# ddrive-esp-deadrail-1-1.net
KiCad netlist of a schematic drawn in EAGLE
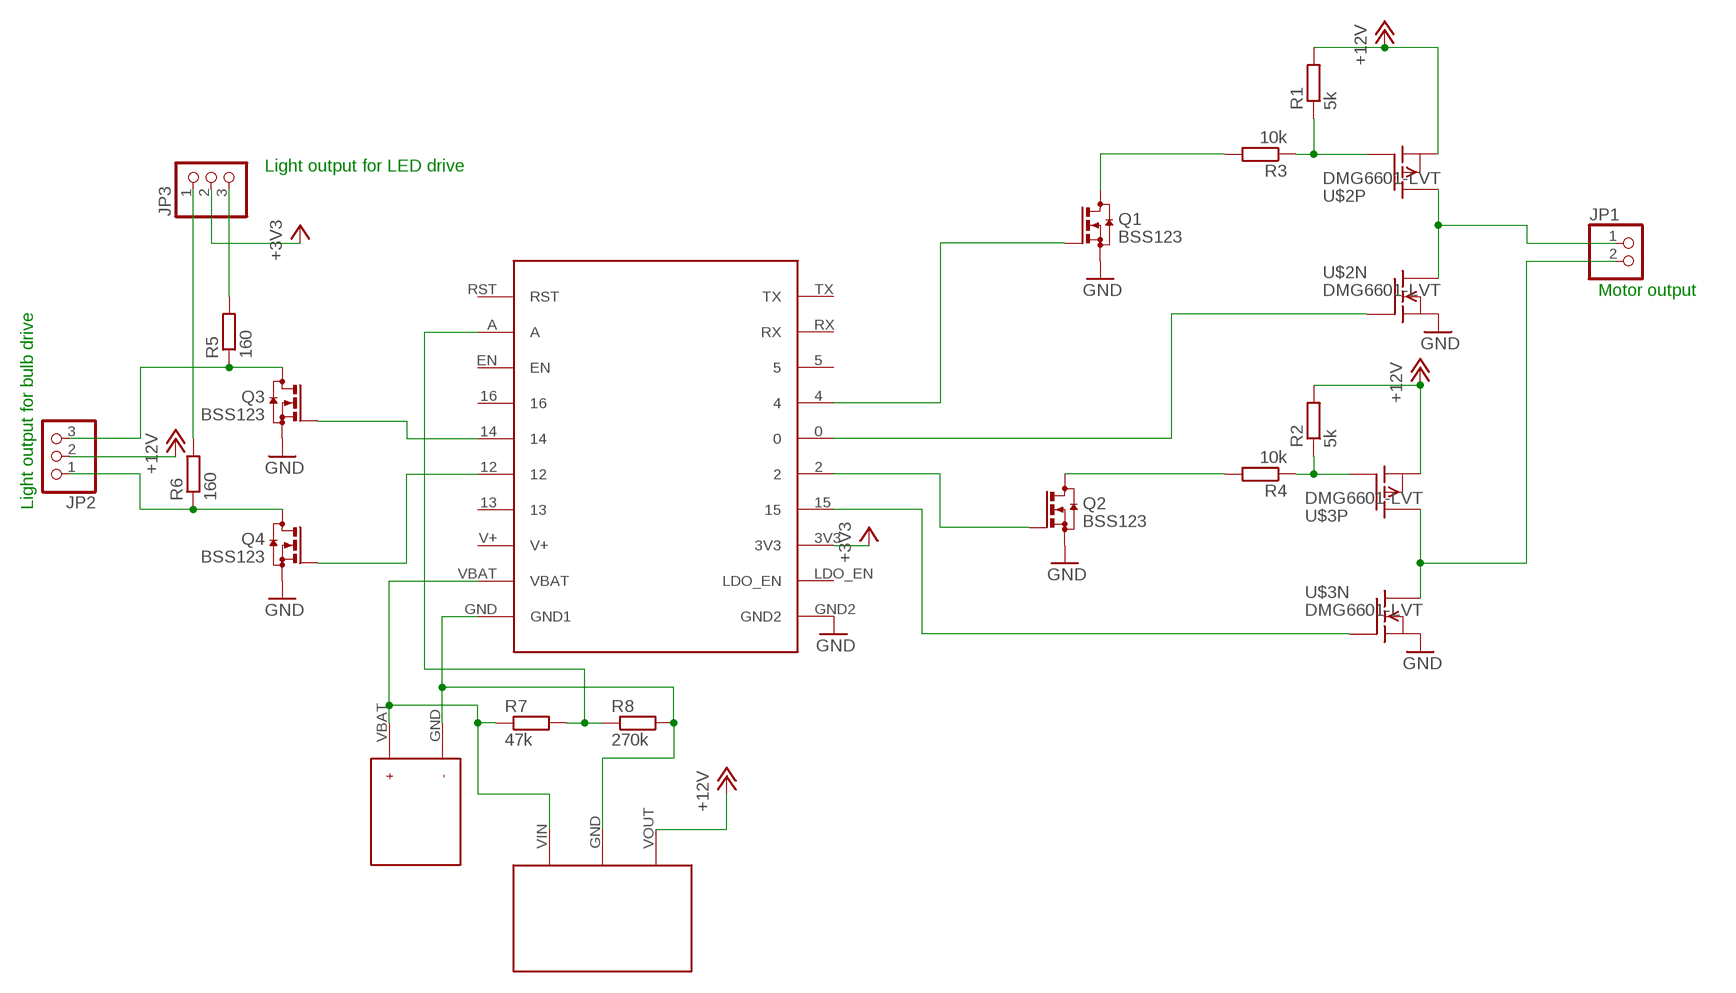
[diagram p0: schematic, sheet 1]

(export (version "E")
  (design (tool "Eeschema 10.0.6"))
  (components
    (comp (ref "JP1")
      (value "PINHD-1X2")
      (footprint "eagle-import:1X02")
      (libsource (lib "eagle-import") (part "PINHD-1X2"))
    )
    (comp (ref "JP2")
      (value "PINHD-1X3")
      (footprint "eagle-import:1X03")
      (libsource (lib "eagle-import") (part "PINHD-1X3"))
    )
    (comp (ref "JP3")
      (value "PINHD-1X3")
      (footprint "eagle-import:1X03")
      (libsource (lib "eagle-import") (part "PINHD-1X3"))
    )
    (comp (ref "Q1")
      (value "BSS123")
      (footprint "eagle-import:SOT23")
      (libsource (lib "eagle-import") (part "BSS123"))
    )
    (comp (ref "Q2")
      (value "BSS123")
      (footprint "eagle-import:SOT23")
      (libsource (lib "eagle-import") (part "BSS123"))
    )
    (comp (ref "Q3")
      (value "BSS123")
      (footprint "eagle-import:SOT23")
      (libsource (lib "eagle-import") (part "BSS123"))
    )
    (comp (ref "Q4")
      (value "BSS123")
      (footprint "eagle-import:SOT23")
      (libsource (lib "eagle-import") (part "BSS123"))
    )
    (comp (ref "R1")
      (value "5k")
      (footprint "eagle-import:R0805")
      (libsource (lib "eagle-import") (part "R-EU_R0805"))
    )
    (comp (ref "R2")
      (value "5k")
      (footprint "eagle-import:R0805")
      (libsource (lib "eagle-import") (part "R-EU_R0805"))
    )
    (comp (ref "R3")
      (value "10k")
      (footprint "eagle-import:R0805")
      (libsource (lib "eagle-import") (part "R-EU_R0805"))
    )
    (comp (ref "R4")
      (value "10k")
      (footprint "eagle-import:R0805")
      (libsource (lib "eagle-import") (part "R-EU_R0805"))
    )
    (comp (ref "R5")
      (value "160")
      (footprint "eagle-import:R0805")
      (libsource (lib "eagle-import") (part "R-EU_R0805"))
    )
    (comp (ref "R6")
      (value "160")
      (footprint "eagle-import:R0805")
      (libsource (lib "eagle-import") (part "R-EU_R0805"))
    )
    (comp (ref "R7")
      (value "47k")
      (footprint "eagle-import:R0805")
      (libsource (lib "eagle-import") (part "R-EU_R0805"))
    )
    (comp (ref "R8")
      (value "270k")
      (footprint "eagle-import:R0805")
      (libsource (lib "eagle-import") (part "R-EU_R0805"))
    )
    (comp (ref "U$1")
      (value "ESP12-HUZZAH")
      (footprint "eagle-import:ESP12-HUZZAH")
      (libsource (lib "eagle-import") (part "ESP12-HUZZAH"))
    )
    (comp (ref "U$2")
      (value "DMG6601-LVT")
      (footprint "eagle-import:TSOT-26")
      (libsource (lib "eagle-import") (part "DMG6601-LVT"))
    )
    (comp (ref "U$3")
      (value "DMG6601-LVT")
      (footprint "eagle-import:TSOT-26")
      (libsource (lib "eagle-import") (part "DMG6601-LVT"))
    )
    (comp (ref "U$4")
      (value "JST-PINHD")
      (footprint "eagle-import:JST-PINHDR")
      (libsource (lib "eagle-import") (part "JST-PINHD"))
    )
    (comp (ref "U$5")
      (value "POLOLU-VREG12")
      (footprint "eagle-import:POLOLU-REGULATOR")
      (libsource (lib "eagle-import") (part "POLOLU-VREG12"))
    )
  )
  (nets
    (net (code "1") (name "+3V3") (class "Default")
      (node (ref "JP3") (pin "2") (pinfunction "2_2") (pintype "passive"))
      (node (ref "U$1") (pin "3V3") (pinfunction "3V3_3V3") (pintype "power_in"))
    )
    (net (code "2") (name "+12V") (class "Default")
      (node (ref "JP2") (pin "2") (pinfunction "2_2") (pintype "passive"))
      (node (ref "R1") (pin "2") (pinfunction "2_2") (pintype "passive"))
      (node (ref "R2") (pin "2") (pinfunction "2_2") (pintype "passive"))
      (node (ref "U$2") (pin "2") (pinfunction "S_2") (pintype "passive"))
      (node (ref "U$3") (pin "2") (pinfunction "S_2") (pintype "passive"))
      (node (ref "U$5") (pin "VOUT") (pinfunction "VOUT_VOUT") (pintype "bidirectional"))
    )
    (net (code "3") (name "/V+") (class "Default")
      (node (ref "U$1") (pin "V+") (pinfunction "V+_V+") (pintype "power_in"))
    )
    (net (code "4") (name "GND") (class "Default")
      (node (ref "Q1") (pin "2") (pinfunction "S_2") (pintype "passive"))
      (node (ref "Q2") (pin "2") (pinfunction "S_2") (pintype "passive"))
      (node (ref "Q3") (pin "2") (pinfunction "S_2") (pintype "passive"))
      (node (ref "Q4") (pin "2") (pinfunction "S_2") (pintype "passive"))
      (node (ref "U$1") (pin "GND2") (pinfunction "GND2_GND2") (pintype "power_in"))
      (node (ref "U$2") (pin "5") (pinfunction "S_5") (pintype "passive"))
      (node (ref "U$3") (pin "5") (pinfunction "S_5") (pintype "passive"))
    )
    (net (code "5") (name "Net-(JP3-Pad1)") (class "Default")
      (node (ref "JP3") (pin "1") (pinfunction "1_1") (pintype "passive"))
      (node (ref "R6") (pin "2") (pinfunction "2_2") (pintype "passive"))
    )
    (net (code "6") (name "Net-(JP3-Pad3)") (class "Default")
      (node (ref "JP3") (pin "3") (pinfunction "3_3") (pintype "passive"))
      (node (ref "R5") (pin "2") (pinfunction "2_2") (pintype "passive"))
    )
    (net (code "7") (name "Net-(Q1-D)") (class "Default")
      (node (ref "Q1") (pin "3") (pinfunction "D_3") (pintype "passive"))
      (node (ref "R3") (pin "2") (pinfunction "2_2") (pintype "passive"))
    )
    (net (code "8") (name "Net-(Q1-G)") (class "Default")
      (node (ref "Q1") (pin "1") (pinfunction "G_1") (pintype "passive"))
      (node (ref "U$1") (pin "4") (pinfunction "4_4") (pintype "bidirectional"))
    )
    (net (code "9") (name "Net-(Q2-D)") (class "Default")
      (node (ref "Q2") (pin "3") (pinfunction "D_3") (pintype "passive"))
      (node (ref "R4") (pin "2") (pinfunction "2_2") (pintype "passive"))
    )
    (net (code "10") (name "Net-(Q2-G)") (class "Default")
      (node (ref "Q2") (pin "1") (pinfunction "G_1") (pintype "passive"))
      (node (ref "U$1") (pin "2") (pinfunction "2_2") (pintype "bidirectional"))
    )
    (net (code "11") (name "Net-(Q3-D)") (class "Default")
      (node (ref "JP2") (pin "3") (pinfunction "3_3") (pintype "passive"))
      (node (ref "Q3") (pin "3") (pinfunction "D_3") (pintype "passive"))
      (node (ref "R5") (pin "1") (pinfunction "1_1") (pintype "passive"))
    )
    (net (code "12") (name "Net-(Q3-G)") (class "Default")
      (node (ref "Q3") (pin "1") (pinfunction "G_1") (pintype "passive"))
      (node (ref "U$1") (pin "14") (pinfunction "14_14") (pintype "bidirectional"))
    )
    (net (code "13") (name "Net-(Q4-D)") (class "Default")
      (node (ref "JP2") (pin "1") (pinfunction "1_1") (pintype "passive"))
      (node (ref "Q4") (pin "3") (pinfunction "D_3") (pintype "passive"))
      (node (ref "R6") (pin "1") (pinfunction "1_1") (pintype "passive"))
    )
    (net (code "14") (name "Net-(Q4-G)") (class "Default")
      (node (ref "Q4") (pin "1") (pinfunction "G_1") (pintype "passive"))
      (node (ref "U$1") (pin "12") (pinfunction "12_12") (pintype "bidirectional"))
    )
    (net (code "15") (name "Net-(R7-Pad2)") (class "Default")
      (node (ref "R7") (pin "2") (pinfunction "2_2") (pintype "passive"))
      (node (ref "R8") (pin "1") (pinfunction "1_1") (pintype "passive"))
      (node (ref "U$1") (pin "A") (pinfunction "A_A") (pintype "bidirectional"))
    )
    (net (code "16") (name "Net-(U$1-GND1)") (class "Default")
      (node (ref "R8") (pin "2") (pinfunction "2_2") (pintype "passive"))
      (node (ref "U$1") (pin "GND") (pinfunction "GND1_GND") (pintype "power_in"))
      (node (ref "U$4") (pin "GND") (pinfunction "P$1_GND") (pintype "power_in"))
      (node (ref "U$5") (pin "GND") (pinfunction "GND_GND") (pintype "bidirectional"))
    )
    (net (code "17") (name "Net-(U$2A-D)") (class "Default")
      (node (ref "JP1") (pin "1") (pinfunction "1_1") (pintype "passive"))
      (node (ref "U$2") (pin "4") (pinfunction "D_4") (pintype "passive"))
      (node (ref "U$2") (pin "6") (pinfunction "D_6") (pintype "passive"))
    )
    (net (code "18") (name "Net-(U$2A-G)") (class "Default")
      (node (ref "U$1") (pin "0") (pinfunction "0_0") (pintype "bidirectional"))
      (node (ref "U$2") (pin "1") (pinfunction "G_1") (pintype "passive"))
    )
    (net (code "19") (name "Net-(U$2B-G)") (class "Default")
      (node (ref "R1") (pin "1") (pinfunction "1_1") (pintype "passive"))
      (node (ref "R3") (pin "1") (pinfunction "1_1") (pintype "passive"))
      (node (ref "U$2") (pin "3") (pinfunction "G_3") (pintype "passive"))
    )
    (net (code "20") (name "Net-(U$3A-D)") (class "Default")
      (node (ref "JP1") (pin "2") (pinfunction "2_2") (pintype "passive"))
      (node (ref "U$3") (pin "4") (pinfunction "D_4") (pintype "passive"))
      (node (ref "U$3") (pin "6") (pinfunction "D_6") (pintype "passive"))
    )
    (net (code "21") (name "Net-(U$3A-G)") (class "Default")
      (node (ref "U$1") (pin "15") (pinfunction "15_15") (pintype "bidirectional"))
      (node (ref "U$3") (pin "1") (pinfunction "G_1") (pintype "passive"))
    )
    (net (code "22") (name "Net-(U$3B-G)") (class "Default")
      (node (ref "R2") (pin "1") (pinfunction "1_1") (pintype "passive"))
      (node (ref "R4") (pin "1") (pinfunction "1_1") (pintype "passive"))
      (node (ref "U$3") (pin "3") (pinfunction "G_3") (pintype "passive"))
    )
    (net (code "23") (name "Net-(U$4-P$2)") (class "Default")
      (node (ref "R7") (pin "1") (pinfunction "1_1") (pintype "passive"))
      (node (ref "U$1") (pin "VBAT") (pinfunction "VBAT_VBAT") (pintype "power_in"))
      (node (ref "U$4") (pin "VBAT") (pinfunction "P$2_VBAT") (pintype "power_in"))
      (node (ref "U$5") (pin "VIN") (pinfunction "VIN_VIN") (pintype "bidirectional"))
    )
    (net (code "24") (name "unconnected-(U$1-Pad5)") (class "Default")
      (node (ref "U$1") (pin "5") (pinfunction "5_5") (pintype "bidirectional"))
    )
    (net (code "25") (name "unconnected-(U$1-Pad13)") (class "Default")
      (node (ref "U$1") (pin "13") (pinfunction "13_13") (pintype "bidirectional"))
    )
    (net (code "26") (name "unconnected-(U$1-Pad16)") (class "Default")
      (node (ref "U$1") (pin "16") (pinfunction "16_16") (pintype "bidirectional"))
    )
    (net (code "27") (name "unconnected-(U$1-PadEN)") (class "Default")
      (node (ref "U$1") (pin "EN") (pinfunction "EN_EN") (pintype "bidirectional"))
    )
    (net (code "28") (name "unconnected-(U$1-PadLDO_EN)") (class "Default")
      (node (ref "U$1") (pin "LDO_EN") (pinfunction "LDO_EN_LDO_EN") (pintype "bidirectional"))
    )
    (net (code "29") (name "unconnected-(U$1-PadRST)") (class "Default")
      (node (ref "U$1") (pin "RST") (pinfunction "RST_RST") (pintype "bidirectional"))
    )
    (net (code "30") (name "unconnected-(U$1-PadRX)") (class "Default")
      (node (ref "U$1") (pin "RX") (pinfunction "RX_RX") (pintype "bidirectional"))
    )
    (net (code "31") (name "unconnected-(U$1-PadTX)") (class "Default")
      (node (ref "U$1") (pin "TX") (pinfunction "TX_TX") (pintype "bidirectional"))
    )
  )
)
